# atividade-02.net
KiCad netlist of a schematic drawn in EAGLE
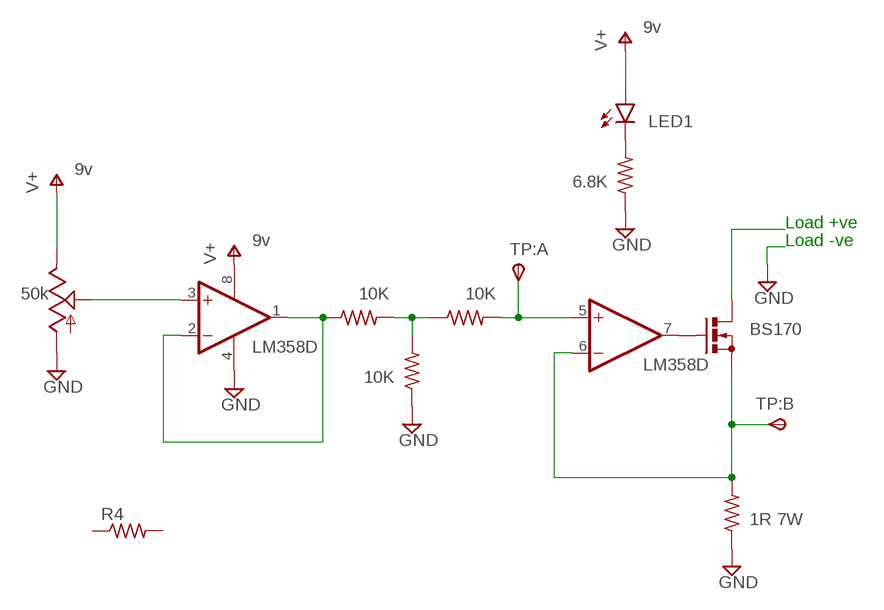
[diagram p0: schematic, sheet 1]

(export (version "E")
  (design (tool "Eeschema 10.0.6"))
  (components
    (comp (ref "IC1")
      (value "LM358D")
      (footprint "eagle-import:SO08")
      (libsource (lib "eagle-import") (part "LM358D"))
    )
    (comp (ref "IC2")
      (value "OP1277RM")
      (footprint "eagle-import:MSOP08")
      (libsource (lib "eagle-import") (part "OP1277RM"))
    )
    (comp (ref "LED1")
      (value "LED5MM")
      (footprint "eagle-import:LED5MM")
      (libsource (lib "eagle-import") (part "LED5MM"))
    )
    (comp (ref "Q1")
      (value "BS170")
      (footprint "eagle-import:SOT54E")
      (libsource (lib "eagle-import") (part "BS170"))
    )
    (comp (ref "R1")
      (value "US-EVUF3J")
      (footprint "eagle-import:EVUFXJ")
      (fields (field (name "LABEL") "50k"))
      (libsource (lib "eagle-import") (part "US-EVUF3J"))
    )
    (comp (ref "R2")
      (value "R-US_WSC0001")
      (footprint "eagle-import:WSC0001")
      (fields (field (name "LABEL") "10K"))
      (libsource (lib "eagle-import") (part "R-US_WSC0001"))
    )
    (comp (ref "R3")
      (value "R-US_WSC0001")
      (footprint "eagle-import:WSC0001")
      (fields (field (name "LABEL") "1R 7W"))
      (libsource (lib "eagle-import") (part "R-US_WSC0001"))
    )
    (comp (ref "R4")
      (value "R-US_WSC0001")
      (footprint "eagle-import:WSC0001")
      (libsource (lib "eagle-import") (part "R-US_WSC0001"))
    )
    (comp (ref "R5")
      (value "R-US_WSC0001")
      (footprint "eagle-import:WSC0001")
      (fields (field (name "LABEL") "10K"))
      (libsource (lib "eagle-import") (part "R-US_WSC0001"))
    )
    (comp (ref "R6")
      (value "R-US_WSC0001")
      (footprint "eagle-import:WSC0001")
      (fields (field (name "LABEL") "10K"))
      (libsource (lib "eagle-import") (part "R-US_WSC0001"))
    )
    (comp (ref "R7")
      (value "R-US_WSC0001")
      (footprint "eagle-import:WSC0001")
      (fields (field (name "LABEL") "6.8K"))
      (libsource (lib "eagle-import") (part "R-US_WSC0001"))
    )
    (comp (ref "TP1")
      (value "TPSPAD1-20Y")
      (footprint "eagle-import:P1-20Y")
      (fields (field (name "TP_SIGNAL_NAME") "TP:A"))
      (libsource (lib "eagle-import") (part "TPSPAD1-20Y"))
    )
    (comp (ref "TP2")
      (value "TPSPAD1-20Y")
      (footprint "eagle-import:P1-20Y")
      (fields (field (name "TP_SIGNAL_NAME") "TP:B"))
      (libsource (lib "eagle-import") (part "TPSPAD1-20Y"))
    )
  )
  (nets
    (net (code "1") (name "GND") (class "Default")
      (node (ref "IC2") (pin "4") (pinfunction "V-_4") (pintype "power_in"))
      (node (ref "R1") (pin "1") (pinfunction "A_1") (pintype "passive"))
      (node (ref "R3") (pin "1") (pinfunction "1_1") (pintype "passive"))
      (node (ref "R6") (pin "1") (pinfunction "1_1") (pintype "passive"))
      (node (ref "R7") (pin "1") (pinfunction "1_1") (pintype "passive"))
    )
    (net (code "2") (name "Net-(IC1A-+IN)") (class "Default")
      (node (ref "IC1") (pin "3") (pinfunction "+IN_3") (pintype "input"))
      (node (ref "R1") (pin "2") (pinfunction "S_2") (pintype "passive"))
    )
    (net (code "3") (name "Net-(IC1A--IN)") (class "Default")
      (node (ref "IC1") (pin "1") (pinfunction "OUT_1") (pintype "output"))
      (node (ref "IC1") (pin "2") (pinfunction "-IN_2") (pintype "input"))
      (node (ref "R2") (pin "1") (pinfunction "1_1") (pintype "passive"))
    )
    (net (code "4") (name "Net-(IC1B-+IN)") (class "Default")
      (node (ref "IC1") (pin "5") (pinfunction "+IN_5") (pintype "input"))
      (node (ref "R5") (pin "2") (pinfunction "2_2") (pintype "passive"))
      (node (ref "TP1") (pin "TP") (pinfunction "PP_TP") (pintype "input"))
    )
    (net (code "5") (name "Net-(IC1B--IN)") (class "Default")
      (node (ref "IC1") (pin "6") (pinfunction "-IN_6") (pintype "input"))
      (node (ref "Q1") (pin "S") (pinfunction "S_S") (pintype "passive"))
      (node (ref "R3") (pin "2") (pinfunction "2_2") (pintype "passive"))
      (node (ref "TP2") (pin "TP") (pinfunction "PP_TP") (pintype "input"))
    )
    (net (code "6") (name "Net-(IC1B-OUT)") (class "Default")
      (node (ref "IC1") (pin "7") (pinfunction "OUT_7") (pintype "output"))
      (node (ref "Q1") (pin "G") (pinfunction "G_G") (pintype "passive"))
    )
    (net (code "7") (name "Net-(LED1-C)") (class "Default")
      (node (ref "LED1") (pin "K") (pinfunction "C_K") (pintype "passive"))
      (node (ref "R7") (pin "2") (pinfunction "2_2") (pintype "passive"))
    )
    (net (code "8") (name "Net-(R2-Pad2)") (class "Default")
      (node (ref "R2") (pin "2") (pinfunction "2_2") (pintype "passive"))
      (node (ref "R5") (pin "1") (pinfunction "1_1") (pintype "passive"))
      (node (ref "R6") (pin "2") (pinfunction "2_2") (pintype "passive"))
    )
    (net (code "9") (name "V+") (class "Default")
      (node (ref "IC2") (pin "8") (pinfunction "V+_8") (pintype "power_in"))
      (node (ref "LED1") (pin "A") (pinfunction "A_A") (pintype "passive"))
      (node (ref "R1") (pin "3") (pinfunction "E_3") (pintype "passive"))
    )
    (net (code "10") (name "unconnected-(Q1-PadD)") (class "Default")
      (node (ref "Q1") (pin "D") (pinfunction "D_D") (pintype "passive"))
    )
    (net (code "11") (name "unconnected-(R4-Pad1)") (class "Default")
      (node (ref "R4") (pin "1") (pinfunction "1_1") (pintype "passive"))
    )
    (net (code "12") (name "unconnected-(R4-Pad2)") (class "Default")
      (node (ref "R4") (pin "2") (pinfunction "2_2") (pintype "passive"))
    )
  )
)
